# Volant5_Back_Button_v1_0.net
KiCad netlist of a schematic drawn in Altium Designer
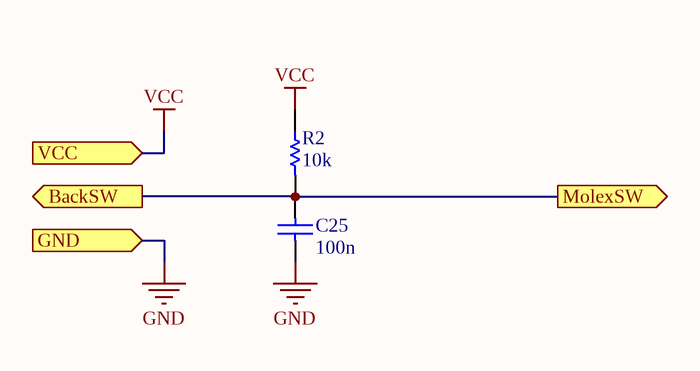
[diagram p0: Volant5.Back_Button_v1.0.SchDoc]

(export (version "E")
  (design (tool "Eeschema 10.0.6"))
  (components
    (comp (ref "C25")
      (value "100n")
      (footprint "CS-0603")
      (fields
        (field (name "VOLTAGE") "16V")
        (field (name "TOLERANCE") "10%")
        (field (name "Comment") "CS - CAPACITOR")
      )
      (libsource (lib "CHINOOK_LIBRARY") (part "CS - CAPACITOR"))
    )
    (comp (ref "R2")
      (value "10k")
      (footprint "RS-0603")
      (fields
        (field (name "POWER") "RES POWER")
        (field (name "TOLERANCE") "RES TOL")
        (field (name "Comment") "RS - RESISTOR")
      )
      (libsource (lib "CHINOOK_LIBRARY") (part "RS - RESISTOR"))
    )
  )
  (nets
    (net (code "1") (name "/BackSW") (class "Default")
      (node (ref "C25") (pin "2") (pinfunction "2_2") (pintype "passive"))
      (node (ref "R2") (pin "2") (pinfunction "2_2") (pintype "passive"))
    )
    (net (code "2") (name "GND") (class "Default")
      (node (ref "C25") (pin "1") (pinfunction "1_1") (pintype "passive"))
    )
    (net (code "3") (name "VCC") (class "Default")
      (node (ref "R2") (pin "1") (pinfunction "1_1") (pintype "passive"))
    )
  )
)
